# Sensor_de_Presen_a.net
KiCad netlist of a schematic drawn in EAGLE
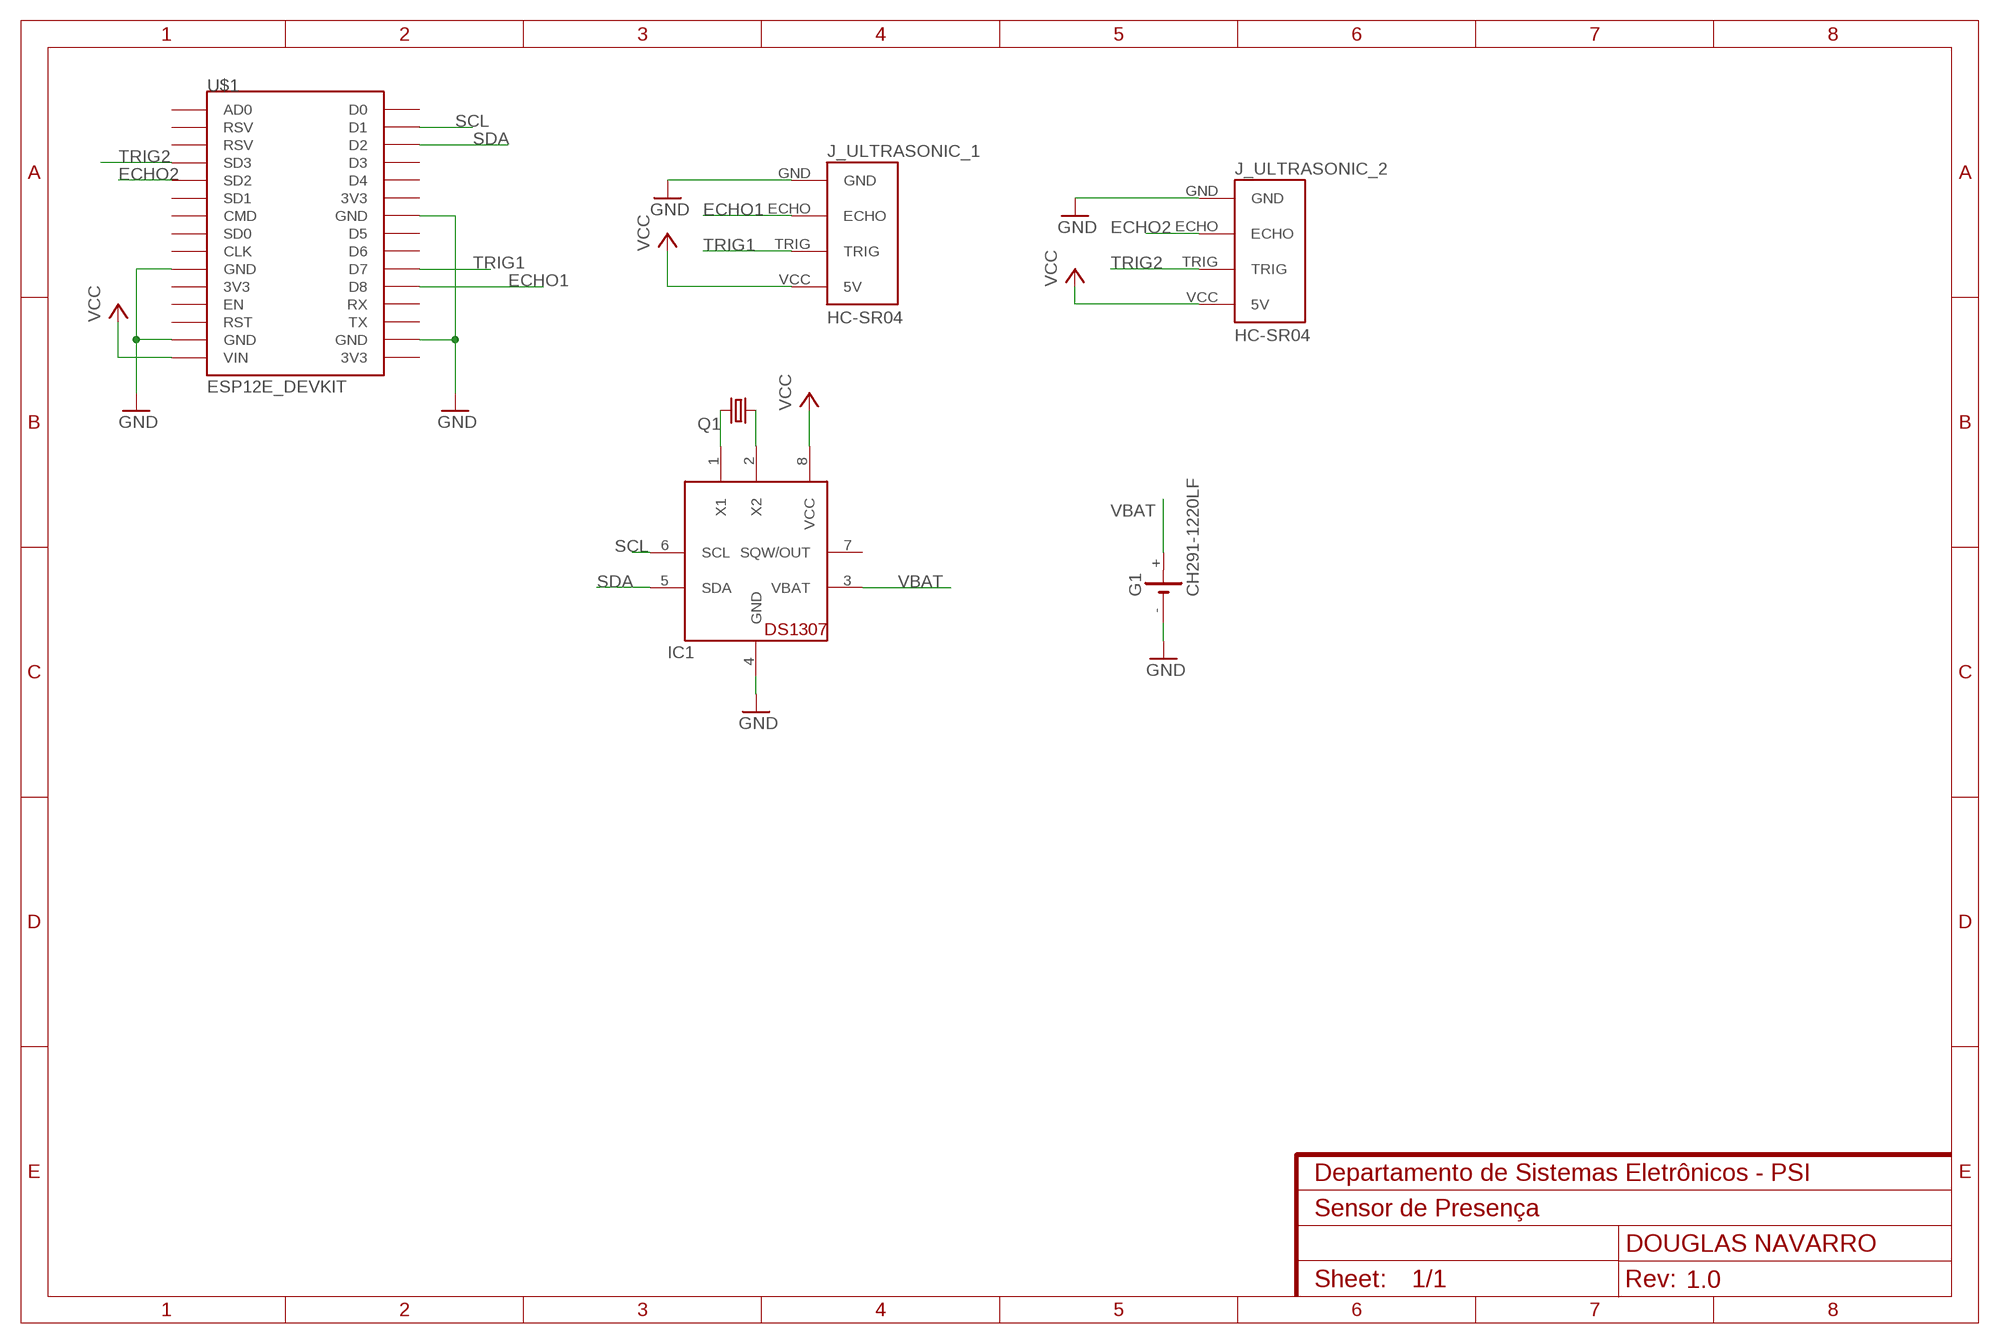
[diagram p0: schematic, sheet 1]

(export (version "E")
  (design (tool "Eeschema 10.0.6"))
  (components
    (comp (ref "G1")
      (value "CH291-1220LF")
      (footprint "eagle-import:CH291-1220LF")
      (libsource (lib "eagle-import") (part "CH291-1220LF"))
    )
    (comp (ref "IC1")
      (value "DS1307")
      (footprint "eagle-import:DIL08")
      (libsource (lib "eagle-import") (part "DS1307"))
    )
    (comp (ref "J_ULTRASONIC_1")
      (value "HC-SR04")
      (footprint "eagle-import:HC-SR04_FOOTPRINT")
      (libsource (lib "eagle-import") (part "HC-SR04"))
    )
    (comp (ref "J_ULTRASONIC_2")
      (value "HC-SR04")
      (footprint "eagle-import:HC-SR04_FOOTPRINT")
      (libsource (lib "eagle-import") (part "HC-SR04"))
    )
    (comp (ref "Q1")
      (value "CRYSTALTC38H")
      (footprint "eagle-import:TC38H")
      (libsource (lib "eagle-import") (part "CRYSTALTC38H"))
    )
    (comp (ref "U$1")
      (value "ESP12E_DEVKIT")
      (footprint "eagle-import:ESP12E_DEVKIT")
      (libsource (lib "eagle-import") (part "ESP12E_DEVKIT"))
    )
  )
  (nets
    (net (code "1") (name "/ECHO1") (class "Default")
      (node (ref "J_ULTRASONIC_1") (pin "ECHO") (pinfunction "ECHO_ECHO") (pintype "bidirectional"))
      (node (ref "U$1") (pin "D8") (pinfunction "D8_D8") (pintype "bidirectional"))
    )
    (net (code "2") (name "/ECHO2") (class "Default")
      (node (ref "J_ULTRASONIC_2") (pin "ECHO") (pinfunction "ECHO_ECHO") (pintype "bidirectional"))
      (node (ref "U$1") (pin "SD2") (pinfunction "SD2_SD2") (pintype "bidirectional"))
    )
    (net (code "3") (name "/SCL") (class "Default")
      (node (ref "IC1") (pin "6") (pinfunction "SCL_6") (pintype "bidirectional"))
      (node (ref "U$1") (pin "D1") (pinfunction "D1_D1") (pintype "bidirectional"))
    )
    (net (code "4") (name "/SDA") (class "Default")
      (node (ref "IC1") (pin "5") (pinfunction "SDA_5") (pintype "bidirectional"))
      (node (ref "U$1") (pin "D2") (pinfunction "D2_D2") (pintype "bidirectional"))
    )
    (net (code "5") (name "/TRIG1") (class "Default")
      (node (ref "J_ULTRASONIC_1") (pin "TRIG") (pinfunction "TRIG_TRIG") (pintype "bidirectional"))
      (node (ref "U$1") (pin "D7") (pinfunction "D7_D7") (pintype "bidirectional"))
    )
    (net (code "6") (name "/TRIG2") (class "Default")
      (node (ref "J_ULTRASONIC_2") (pin "TRIG") (pinfunction "TRIG_TRIG") (pintype "bidirectional"))
      (node (ref "U$1") (pin "SD3") (pinfunction "SD3_SD3") (pintype "bidirectional"))
    )
    (net (code "7") (name "/VBAT") (class "Default")
      (node (ref "G1") (pin "+") (pinfunction "+_+") (pintype "passive"))
      (node (ref "IC1") (pin "3") (pinfunction "VBAT_3") (pintype "power_in"))
    )
    (net (code "8") (name "GND") (class "Default")
      (node (ref "G1") (pin "-") (pinfunction "-_-") (pintype "passive"))
      (node (ref "IC1") (pin "4") (pinfunction "GND_4") (pintype "power_in"))
      (node (ref "J_ULTRASONIC_1") (pin "GND") (pinfunction "GND_GND") (pintype "bidirectional"))
      (node (ref "J_ULTRASONIC_2") (pin "GND") (pinfunction "GND_GND") (pintype "bidirectional"))
      (node (ref "U$1") (pin "GND@0") (pinfunction "GND_GND@0") (pintype "bidirectional"))
      (node (ref "U$1") (pin "GND@1") (pinfunction "GND_GND@1") (pintype "bidirectional"))
      (node (ref "U$1") (pin "GND@2") (pinfunction "GND_GND@2") (pintype "bidirectional"))
      (node (ref "U$1") (pin "GND@3") (pinfunction "GND_GND@3") (pintype "bidirectional"))
    )
    (net (code "9") (name "Net-(IC1-X1)") (class "Default")
      (node (ref "IC1") (pin "1") (pinfunction "X1_1") (pintype "passive"))
      (node (ref "Q1") (pin "2") (pinfunction "2_2") (pintype "passive"))
    )
    (net (code "10") (name "Net-(IC1-X2)") (class "Default")
      (node (ref "IC1") (pin "2") (pinfunction "X2_2") (pintype "passive"))
      (node (ref "Q1") (pin "1") (pinfunction "1_1") (pintype "passive"))
    )
    (net (code "11") (name "VCC") (class "Default")
      (node (ref "IC1") (pin "8") (pinfunction "VCC_8") (pintype "power_in"))
      (node (ref "J_ULTRASONIC_1") (pin "VCC") (pinfunction "5V_VCC") (pintype "bidirectional"))
      (node (ref "J_ULTRASONIC_2") (pin "VCC") (pinfunction "5V_VCC") (pintype "bidirectional"))
      (node (ref "U$1") (pin "VIN") (pinfunction "VIN_VIN") (pintype "bidirectional"))
    )
    (net (code "12") (name "unconnected-(IC1-SQW{slash}OUT-Pad7)") (class "Default")
      (node (ref "IC1") (pin "7") (pinfunction "SQW/OUT_7") (pintype "bidirectional"))
    )
    (net (code "13") (name "unconnected-(U$1-3V3-Pad3V3@0)") (class "Default")
      (node (ref "U$1") (pin "3V3@0") (pinfunction "3V3_3V3@0") (pintype "bidirectional"))
    )
    (net (code "14") (name "unconnected-(U$1-3V3-Pad3V3@1)") (class "Default")
      (node (ref "U$1") (pin "3V3@1") (pinfunction "3V3_3V3@1") (pintype "bidirectional"))
    )
    (net (code "15") (name "unconnected-(U$1-3V3-Pad3V3@2)") (class "Default")
      (node (ref "U$1") (pin "3V3@2") (pinfunction "3V3_3V3@2") (pintype "bidirectional"))
    )
    (net (code "16") (name "unconnected-(U$1-PadAD0)") (class "Default")
      (node (ref "U$1") (pin "AD0") (pinfunction "AD0_AD0") (pintype "bidirectional"))
    )
    (net (code "17") (name "unconnected-(U$1-PadCLK)") (class "Default")
      (node (ref "U$1") (pin "CLK") (pinfunction "CLK_CLK") (pintype "bidirectional"))
    )
    (net (code "18") (name "unconnected-(U$1-PadCMD)") (class "Default")
      (node (ref "U$1") (pin "CMD") (pinfunction "CMD_CMD") (pintype "bidirectional"))
    )
    (net (code "19") (name "unconnected-(U$1-PadD0)") (class "Default")
      (node (ref "U$1") (pin "D0") (pinfunction "D0_D0") (pintype "bidirectional"))
    )
    (net (code "20") (name "unconnected-(U$1-PadD3)") (class "Default")
      (node (ref "U$1") (pin "D3") (pinfunction "D3_D3") (pintype "bidirectional"))
    )
    (net (code "21") (name "unconnected-(U$1-PadD4)") (class "Default")
      (node (ref "U$1") (pin "D4") (pinfunction "D4_D4") (pintype "bidirectional"))
    )
    (net (code "22") (name "unconnected-(U$1-PadD5)") (class "Default")
      (node (ref "U$1") (pin "D5") (pinfunction "D5_D5") (pintype "bidirectional"))
    )
    (net (code "23") (name "unconnected-(U$1-PadD6)") (class "Default")
      (node (ref "U$1") (pin "D6") (pinfunction "D6_D6") (pintype "bidirectional"))
    )
    (net (code "24") (name "unconnected-(U$1-PadEN)") (class "Default")
      (node (ref "U$1") (pin "EN") (pinfunction "EN_EN") (pintype "bidirectional"))
    )
    (net (code "25") (name "unconnected-(U$1-PadRST)") (class "Default")
      (node (ref "U$1") (pin "RST") (pinfunction "RST_RST") (pintype "bidirectional"))
    )
    (net (code "26") (name "unconnected-(U$1-PadRX)") (class "Default")
      (node (ref "U$1") (pin "RX") (pinfunction "RX_RX") (pintype "bidirectional"))
    )
    (net (code "27") (name "unconnected-(U$1-PadSD0)") (class "Default")
      (node (ref "U$1") (pin "SD0") (pinfunction "SD0_SD0") (pintype "bidirectional"))
    )
    (net (code "28") (name "unconnected-(U$1-PadSD1)") (class "Default")
      (node (ref "U$1") (pin "SD1") (pinfunction "SD1_SD1") (pintype "bidirectional"))
    )
    (net (code "29") (name "unconnected-(U$1-PadTX)") (class "Default")
      (node (ref "U$1") (pin "TX") (pinfunction "TX_TX") (pintype "bidirectional"))
    )
    (net (code "30") (name "unconnected-(U$1-RSV-PadRSV@0)") (class "Default")
      (node (ref "U$1") (pin "RSV@0") (pinfunction "RSV_RSV@0") (pintype "bidirectional"))
    )
    (net (code "31") (name "unconnected-(U$1-RSV-PadRSV@1)") (class "Default")
      (node (ref "U$1") (pin "RSV@1") (pinfunction "RSV_RSV@1") (pintype "bidirectional"))
    )
  )
)
